# MUDE_-_Rev_A.net
KiCad netlist of a schematic drawn in EAGLE
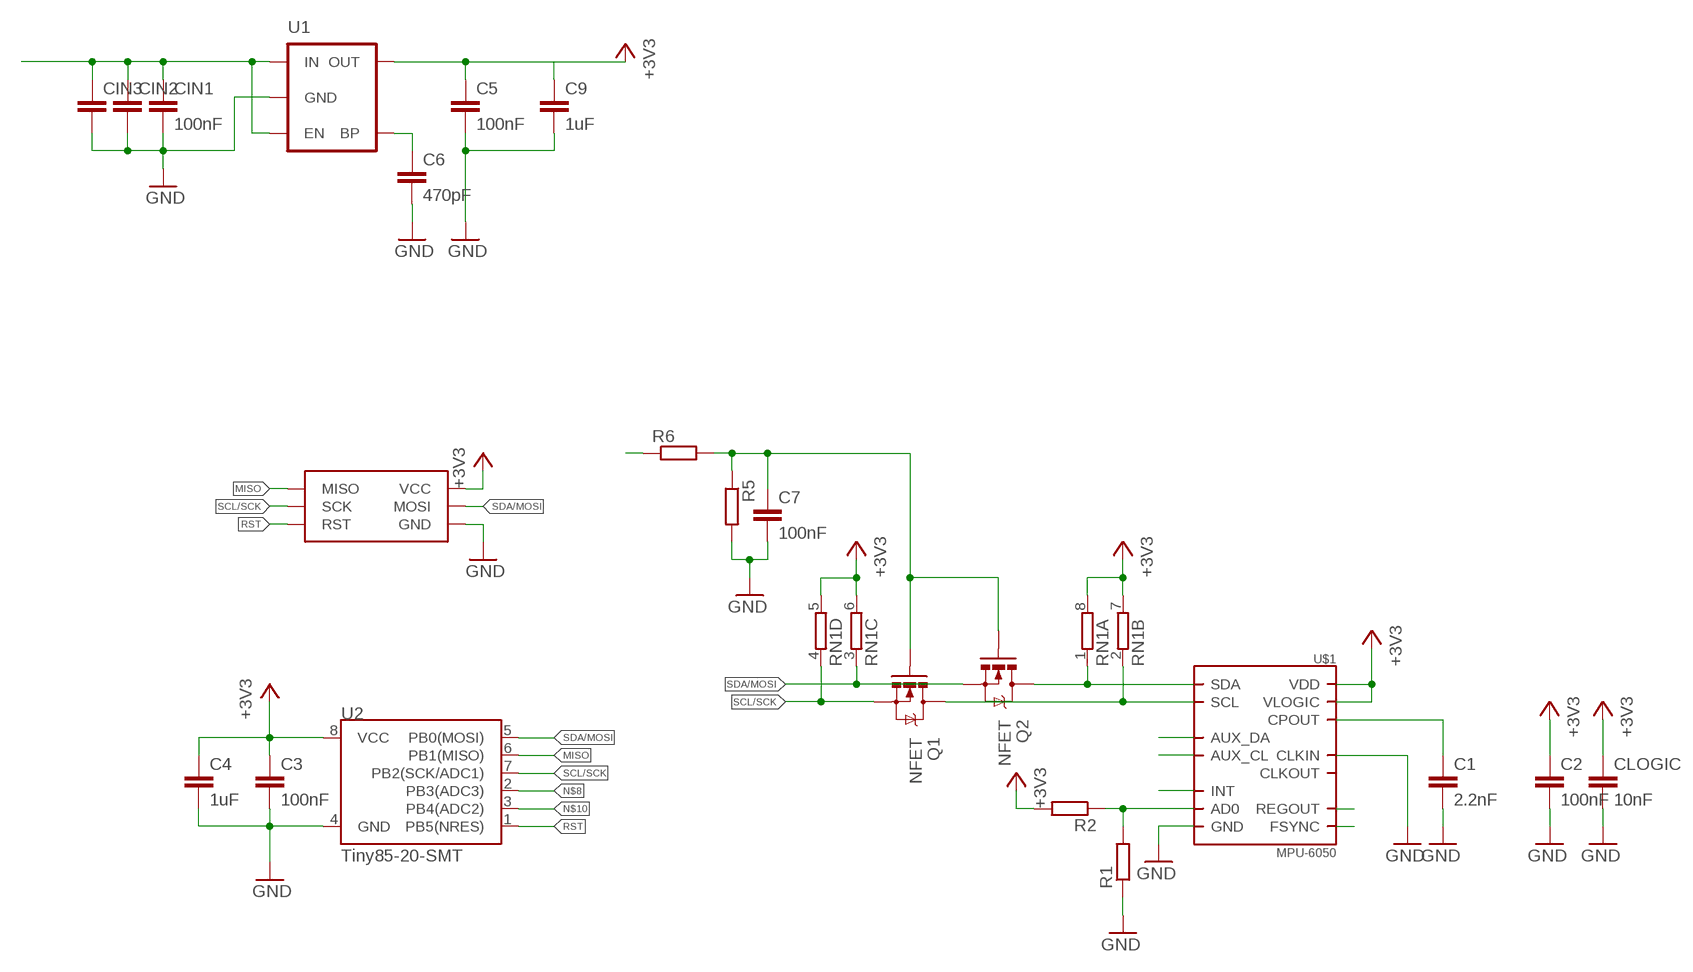
[diagram p0: schematic, sheet 1]

(export (version "E")
  (design (tool "Eeschema 10.0.6"))
  (components
    (comp (ref "C1")
      (value "2.2nF")
      (footprint "eagle-import:C0603")
      (libsource (lib "eagle-import") (part "C-EUC0603"))
    )
    (comp (ref "C2")
      (value "100nF")
      (footprint "eagle-import:C0603")
      (libsource (lib "eagle-import") (part "C-EUC0603"))
    )
    (comp (ref "C3")
      (value "100nF")
      (footprint "eagle-import:C0603")
      (libsource (lib "eagle-import") (part "C-EUC0603"))
    )
    (comp (ref "C4")
      (value "1uF")
      (footprint "eagle-import:C0603")
      (libsource (lib "eagle-import") (part "C-EUC0603"))
    )
    (comp (ref "C5")
      (value "100nF")
      (footprint "eagle-import:C0603")
      (libsource (lib "eagle-import") (part "C-EUC0603"))
    )
    (comp (ref "C6")
      (value "470pF")
      (footprint "eagle-import:C0603")
      (libsource (lib "eagle-import") (part "C-EUC0603"))
    )
    (comp (ref "C7")
      (value "100nF")
      (footprint "eagle-import:C0603")
      (libsource (lib "eagle-import") (part "C-EUC0603"))
    )
    (comp (ref "C9")
      (value "1uF")
      (footprint "eagle-import:C0603")
      (libsource (lib "eagle-import") (part "C-EUC0603"))
    )
    (comp (ref "CIN1")
      (value "100nF")
      (footprint "eagle-import:C0603")
      (libsource (lib "eagle-import") (part "C-EUC0603"))
    )
    (comp (ref "CIN2")
      (value "C-EUC0805")
      (footprint "eagle-import:C0805")
      (libsource (lib "eagle-import") (part "C-EUC0805"))
    )
    (comp (ref "CIN3")
      (value "C-EUC0805")
      (footprint "eagle-import:C0805")
      (libsource (lib "eagle-import") (part "C-EUC0805"))
    )
    (comp (ref "CLOGIC")
      (value "10nF")
      (footprint "eagle-import:C0603")
      (libsource (lib "eagle-import") (part "C-EUC0603"))
    )
    (comp (ref "Q1")
      (value "NFET")
      (footprint "eagle-import:SOT23")
      (libsource (lib "eagle-import") (part "MOSFET-NCHANNELBSS123LT1G"))
    )
    (comp (ref "Q2")
      (value "NFET")
      (footprint "eagle-import:SOT23")
      (libsource (lib "eagle-import") (part "MOSFET-NCHANNELBSS123LT1G"))
    )
    (comp (ref "R1")
      (value "R-EU_R0603")
      (footprint "eagle-import:R0603")
      (libsource (lib "eagle-import") (part "R-EU_R0603"))
    )
    (comp (ref "R2")
      (value "R-EU_R0603")
      (footprint "eagle-import:R0603")
      (libsource (lib "eagle-import") (part "R-EU_R0603"))
    )
    (comp (ref "R5")
      (value "R-EU_R0603")
      (footprint "eagle-import:R0603")
      (libsource (lib "eagle-import") (part "R-EU_R0603"))
    )
    (comp (ref "R6")
      (value "R-EU_R0603")
      (footprint "eagle-import:R0603")
      (libsource (lib "eagle-import") (part "R-EU_R0603"))
    )
    (comp (ref "RN1")
      (value "4R-N0603-ARV")
      (footprint "eagle-import:0603-ARV")
      (libsource (lib "eagle-import") (part "4R-N0603-ARV"))
    )
    (comp (ref "U$1")
      (value "MPU-6050")
      (footprint "eagle-import:QFN.24.4X4")
      (libsource (lib "eagle-import") (part "MPU-6050"))
    )
    (comp (ref "U$3")
      (value "ISP_POGOISP_POGO")
      (footprint "eagle-import:ISP_POGO")
      (libsource (lib "eagle-import") (part "ISP_POGOISP_POGO"))
    )
    (comp (ref "U1")
      (value "MIC52053.3V")
      (footprint "eagle-import:SOT23-5")
      (libsource (lib "eagle-import") (part "MIC52053.3V"))
    )
    (comp (ref "U2")
      (value "Tiny85-20-SMT")
      (footprint "eagle-import:SO08-EIAJ")
      (libsource (lib "eagle-import") (part "ATTINY45TINY85-20-SMT"))
    )
  )
  (nets
    (net (code "1") (name "+3V3") (class "Default")
      (node (ref "C2") (pin "1") (pinfunction "1_1") (pintype "passive"))
      (node (ref "C3") (pin "1") (pinfunction "1_1") (pintype "passive"))
      (node (ref "C4") (pin "1") (pinfunction "1_1") (pintype "passive"))
      (node (ref "C5") (pin "1") (pinfunction "1_1") (pintype "passive"))
      (node (ref "C9") (pin "1") (pinfunction "1_1") (pintype "passive"))
      (node (ref "CLOGIC") (pin "1") (pinfunction "1_1") (pintype "passive"))
      (node (ref "R2") (pin "2") (pinfunction "2_2") (pintype "passive"))
      (node (ref "RN1") (pin "5") (pinfunction "2_5") (pintype "passive"))
      (node (ref "RN1") (pin "6") (pinfunction "2_6") (pintype "passive"))
      (node (ref "RN1") (pin "7") (pinfunction "2_7") (pintype "passive"))
      (node (ref "RN1") (pin "8") (pinfunction "2_8") (pintype "passive"))
      (node (ref "U$1") (pin "13") (pinfunction "VDD_13") (pintype "bidirectional"))
      (node (ref "U$1") (pin "8") (pinfunction "VLOGIC_8") (pintype "bidirectional"))
      (node (ref "U$3") (pin "VCC") (pinfunction "VCC_VCC") (pintype "bidirectional"))
      (node (ref "U1") (pin "5") (pinfunction "OUT_5") (pintype "passive"))
      (node (ref "U2") (pin "8") (pinfunction "VCC_8") (pintype "bidirectional"))
    )
    (net (code "2") (name "GND") (class "Default")
      (node (ref "C1") (pin "2") (pinfunction "2_2") (pintype "passive"))
      (node (ref "C2") (pin "2") (pinfunction "2_2") (pintype "passive"))
      (node (ref "C3") (pin "2") (pinfunction "2_2") (pintype "passive"))
      (node (ref "C4") (pin "2") (pinfunction "2_2") (pintype "passive"))
      (node (ref "C5") (pin "2") (pinfunction "2_2") (pintype "passive"))
      (node (ref "C6") (pin "2") (pinfunction "2_2") (pintype "passive"))
      (node (ref "C7") (pin "2") (pinfunction "2_2") (pintype "passive"))
      (node (ref "C9") (pin "2") (pinfunction "2_2") (pintype "passive"))
      (node (ref "CIN1") (pin "2") (pinfunction "2_2") (pintype "passive"))
      (node (ref "CIN2") (pin "2") (pinfunction "2_2") (pintype "passive"))
      (node (ref "CIN3") (pin "2") (pinfunction "2_2") (pintype "passive"))
      (node (ref "CLOGIC") (pin "2") (pinfunction "2_2") (pintype "passive"))
      (node (ref "R1") (pin "1") (pinfunction "1_1") (pintype "passive"))
      (node (ref "R5") (pin "2") (pinfunction "2_2") (pintype "passive"))
      (node (ref "U$1") (pin "1") (pinfunction "CLKIN_1") (pintype "bidirectional"))
      (node (ref "U$1") (pin "18") (pinfunction "GND_18") (pintype "bidirectional"))
      (node (ref "U$3") (pin "GND") (pinfunction "GND_GND") (pintype "bidirectional"))
      (node (ref "U1") (pin "2") (pinfunction "GND_2") (pintype "input"))
      (node (ref "U2") (pin "4") (pinfunction "GND_4") (pintype "bidirectional"))
    )
    (net (code "3") (name "MISO") (class "Default")
      (node (ref "U$3") (pin "MISO") (pinfunction "MISO_MISO") (pintype "bidirectional"))
      (node (ref "U2") (pin "6") (pinfunction "PB1(MISO)_6") (pintype "bidirectional"))
    )
    (net (code "4") (name "N$8") (class "Default")
      (node (ref "U2") (pin "2") (pinfunction "PB3(ADC3)_2") (pintype "bidirectional"))
    )
    (net (code "5") (name "N$10") (class "Default")
      (node (ref "U2") (pin "3") (pinfunction "PB4(ADC2)_3") (pintype "bidirectional"))
    )
    (net (code "6") (name "Net-(Q1-D)") (class "Default")
      (node (ref "Q1") (pin "3") (pinfunction "D_3") (pintype "passive"))
      (node (ref "RN1") (pin "2") (pinfunction "1_2") (pintype "passive"))
      (node (ref "U$1") (pin "23") (pinfunction "SCL_23") (pintype "bidirectional"))
    )
    (net (code "7") (name "Net-(Q1-G)") (class "Default")
      (node (ref "C7") (pin "1") (pinfunction "1_1") (pintype "passive"))
      (node (ref "Q1") (pin "1") (pinfunction "G_1") (pintype "passive"))
      (node (ref "Q2") (pin "1") (pinfunction "G_1") (pintype "passive"))
      (node (ref "R5") (pin "1") (pinfunction "1_1") (pintype "passive"))
      (node (ref "R6") (pin "2") (pinfunction "2_2") (pintype "passive"))
    )
    (net (code "8") (name "Net-(Q2-D)") (class "Default")
      (node (ref "Q2") (pin "3") (pinfunction "D_3") (pintype "passive"))
      (node (ref "RN1") (pin "1") (pinfunction "1_1") (pintype "passive"))
      (node (ref "U$1") (pin "24") (pinfunction "SDA_24") (pintype "bidirectional"))
    )
    (net (code "9") (name "Net-(U$1-AD0)") (class "Default")
      (node (ref "R1") (pin "2") (pinfunction "2_2") (pintype "passive"))
      (node (ref "R2") (pin "1") (pinfunction "1_1") (pintype "passive"))
      (node (ref "U$1") (pin "9") (pinfunction "AD0_9") (pintype "bidirectional"))
    )
    (net (code "10") (name "Net-(U$1-CPOUT)") (class "Default")
      (node (ref "C1") (pin "1") (pinfunction "1_1") (pintype "passive"))
      (node (ref "U$1") (pin "20") (pinfunction "CPOUT_20") (pintype "bidirectional"))
    )
    (net (code "11") (name "Net-(U1-BP)") (class "Default")
      (node (ref "C6") (pin "1") (pinfunction "1_1") (pintype "passive"))
      (node (ref "U1") (pin "4") (pinfunction "BP_4") (pintype "input"))
    )
    (net (code "12") (name "Net-(U1-EN)") (class "Default")
      (node (ref "CIN1") (pin "1") (pinfunction "1_1") (pintype "passive"))
      (node (ref "CIN2") (pin "1") (pinfunction "1_1") (pintype "passive"))
      (node (ref "CIN3") (pin "1") (pinfunction "1_1") (pintype "passive"))
      (node (ref "U1") (pin "1") (pinfunction "IN_1") (pintype "input"))
      (node (ref "U1") (pin "3") (pinfunction "EN_3") (pintype "input"))
    )
    (net (code "13") (name "RST") (class "Default")
      (node (ref "U$3") (pin "RST") (pinfunction "RST_RST") (pintype "bidirectional"))
      (node (ref "U2") (pin "1") (pinfunction "PB5(NRES)_1") (pintype "bidirectional"))
    )
    (net (code "14") (name "SCL{slash}SCK") (class "Default")
      (node (ref "Q1") (pin "2") (pinfunction "S_2") (pintype "passive"))
      (node (ref "RN1") (pin "4") (pinfunction "1_4") (pintype "passive"))
      (node (ref "U$3") (pin "SCK") (pinfunction "SCK_SCK") (pintype "bidirectional"))
      (node (ref "U2") (pin "7") (pinfunction "PB2(SCK/ADC1)_7") (pintype "bidirectional"))
    )
    (net (code "15") (name "SDA{slash}MOSI") (class "Default")
      (node (ref "Q2") (pin "2") (pinfunction "S_2") (pintype "passive"))
      (node (ref "RN1") (pin "3") (pinfunction "1_3") (pintype "passive"))
      (node (ref "U$3") (pin "MOSI") (pinfunction "MOSI_MOSI") (pintype "bidirectional"))
      (node (ref "U2") (pin "5") (pinfunction "PB0(MOSI)_5") (pintype "bidirectional"))
    )
    (net (code "16") (name "unconnected-(R6-Pad1)") (class "Default")
      (node (ref "R6") (pin "1") (pinfunction "1_1") (pintype "passive"))
    )
    (net (code "17") (name "unconnected-(U$1-AUX_CL-Pad7)") (class "Default")
      (node (ref "U$1") (pin "7") (pinfunction "AUX_CL_7") (pintype "bidirectional"))
    )
    (net (code "18") (name "unconnected-(U$1-AUX_DA-Pad6)") (class "Default")
      (node (ref "U$1") (pin "6") (pinfunction "AUX_DA_6") (pintype "bidirectional"))
    )
    (net (code "19") (name "unconnected-(U$1-CLKOUT-Pad22)") (class "Default")
      (node (ref "U$1") (pin "22") (pinfunction "CLKOUT_22") (pintype "bidirectional"))
    )
    (net (code "20") (name "unconnected-(U$1-FSYNC-Pad11)") (class "Default")
      (node (ref "U$1") (pin "11") (pinfunction "FSYNC_11") (pintype "bidirectional"))
    )
    (net (code "21") (name "unconnected-(U$1-INT-Pad12)") (class "Default")
      (node (ref "U$1") (pin "12") (pinfunction "INT_12") (pintype "bidirectional"))
    )
    (net (code "22") (name "unconnected-(U$1-REGOUT-Pad10)") (class "Default")
      (node (ref "U$1") (pin "10") (pinfunction "REGOUT_10") (pintype "bidirectional"))
    )
  )
)
